# Heating.net
KiCad netlist of a schematic drawn in Altium Designer
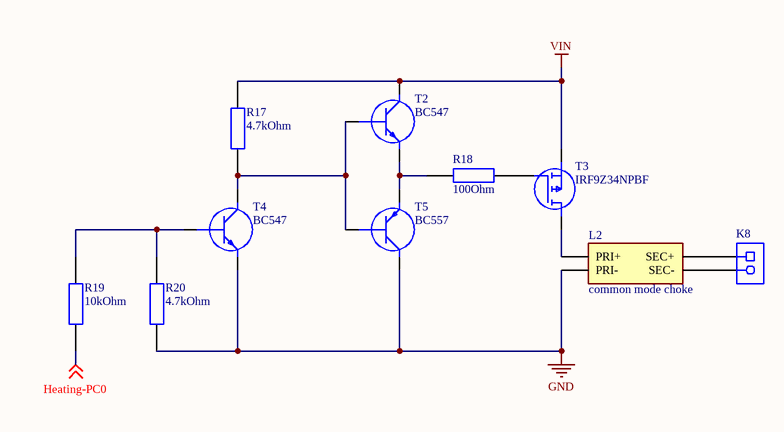
[diagram p0: Heating.SchDoc]

(export (version "E")
  (design (tool "Eeschema 10.0.6"))
  (components
    (comp (ref "K8")
      (value "1729128")
      (footprint "2-pin terminal block")
      (description "PCB Terminal Block, 13.5 A, 400 V, 2-Pin THD, RoHS, Bulk")
      (fields (field (name "MANUFACTURER") "Phoenix Contact"))
      (libsource (lib "Schlib1") (part "MKDSN 1,5/ 2-5,08"))
    )
    (comp (ref "L2")
      (value "common mode choke")
      (footprint "common mode choke")
      (description "Inductor")
      (fields (field (name "MANUFACTURER_PART_NUMBER") "CM2545X171B-10"))
      (libsource (lib "Schlib1") (part "common mode choke"))
    )
    (comp (ref "R17")
      (value "4.7kOhm")
      (footprint "resistor")
      (description "Resistor")
      (fields
        (field (name "MOUSER2 PART NUMBER") "603-CFR-25JT-52-4K7")
        (field (name "MANUFACTURER_PART_NUMBER") "CFR-25JT-52-4K7")
      )
      (libsource (lib "Schlib1") (part "4.7kOhm resistor"))
    )
    (comp (ref "R18")
      (value "100Ohm")
      (footprint "resistor")
      (description "Resistor")
      (fields
        (field (name "MOUSER2 PART NUMBER") "603-CFR-25JR-52100R")
        (field (name "MANUFACTURER_PART_NUMBER") "CFR-25JR-52-100R")
      )
      (libsource (lib "Schlib1") (part "100Ohm resistor"))
    )
    (comp (ref "R19")
      (value "10kOhm")
      (footprint "resistor")
      (description "Resistor")
      (fields (field (name "MANUFACTURER_PART_NUMBER") "CFR-25JT-52-10K"))
      (libsource (lib "Schlib1") (part "10kOhm resistor"))
    )
    (comp (ref "R20")
      (value "4.7kOhm")
      (footprint "resistor")
      (description "Resistor")
      (fields
        (field (name "MOUSER2 PART NUMBER") "603-CFR-25JT-52-4K7")
        (field (name "MANUFACTURER_PART_NUMBER") "CFR-25JT-52-4K7")
      )
      (libsource (lib "Schlib1") (part "4.7kOhm resistor"))
    )
    (comp (ref "T2")
      (value "BC547")
      (footprint "PcbLib1:BC547CBU")
      (description "Transistor BJT NPN")
      (fields (field (name "MANUFACTURER_PART_NUMBER") "BC547CBU"))
      (libsource (lib "Schlib1") (part "BC547"))
    )
    (comp (ref "T3")
      (value "IRF9Z34NPBF")
      (footprint "PcbLib1:TO254P469X1042X1967-3P")
      (description "MOSFET (P-Channel)")
      (fields (field (name "MOUSER2 PART NUMBER") "942-IRF9Z34NPBF"))
      (libsource (lib "Schlib1") (part "IRF9Z34NPBF"))
    )
    (comp (ref "T4")
      (value "BC547")
      (footprint "PcbLib1:BC547CBU")
      (description "Transistor BJT NPN")
      (fields (field (name "MANUFACTURER_PART_NUMBER") "BC547CBU"))
      (libsource (lib "Schlib1") (part "BC547"))
    )
    (comp (ref "T5")
      (value "BC557")
      (footprint "PcbLib1:BC33740TA")
      (description "Transistor BJT PNP")
      (fields
        (field (name "MOUSER2 PART NUMBER") "512-BC557ATA")
        (field (name "MANUFACTURER_PART_NUMBER") "BC557ATA")
      )
      (libsource (lib "Schlib1") (part "BC557"))
    )
  )
  (nets
    (net (code "1") (name "GND") (class "Default")
      (node (ref "L2") (pin "4") (pinfunction "PRI-_4") (pintype "passive"))
      (node (ref "R20") (pin "1") (pinfunction "1_1") (pintype "passive"))
      (node (ref "T4") (pin "3") (pinfunction "E_3") (pintype "passive"))
      (node (ref "T5") (pin "1") (pinfunction "C_1") (pintype "passive"))
    )
    (net (code "2") (name "Heating-PC0") (class "Default")
      (node (ref "R19") (pin "2") (pinfunction "2_2") (pintype "passive"))
    )
    (net (code "3") (name "Net-(L2-PRI+)") (class "Default")
      (node (ref "L2") (pin "1") (pinfunction "PRI+_1") (pintype "passive"))
      (node (ref "T3") (pin "3") (pinfunction "D_3") (pintype "passive"))
    )
    (net (code "4") (name "Net-(L2-SEC+)") (class "Default")
      (node (ref "K8") (pin "1") (pinfunction "1_1") (pintype "passive"))
      (node (ref "L2") (pin "2") (pinfunction "SEC+_2") (pintype "passive"))
    )
    (net (code "5") (name "Net-(L2-SEC-)") (class "Default")
      (node (ref "K8") (pin "2") (pinfunction "2_2") (pintype "passive"))
      (node (ref "L2") (pin "3") (pinfunction "SEC-_3") (pintype "passive"))
    )
    (net (code "6") (name "Net-(T2-B)") (class "Default")
      (node (ref "R17") (pin "1") (pinfunction "1_1") (pintype "passive"))
      (node (ref "T2") (pin "2") (pinfunction "B_2") (pintype "passive"))
      (node (ref "T4") (pin "1") (pinfunction "C_1") (pintype "passive"))
      (node (ref "T5") (pin "2") (pinfunction "B_2") (pintype "passive"))
    )
    (net (code "7") (name "Net-(T2-E)") (class "Default")
      (node (ref "R18") (pin "1") (pinfunction "1_1") (pintype "passive"))
      (node (ref "T2") (pin "3") (pinfunction "E_3") (pintype "passive"))
      (node (ref "T5") (pin "3") (pinfunction "E_3") (pintype "passive"))
    )
    (net (code "8") (name "Net-(T3-G)") (class "Default")
      (node (ref "R18") (pin "2") (pinfunction "2_2") (pintype "passive"))
      (node (ref "T3") (pin "1") (pinfunction "G_1") (pintype "passive"))
    )
    (net (code "9") (name "Net-(T4-B)") (class "Default")
      (node (ref "R19") (pin "1") (pinfunction "1_1") (pintype "passive"))
      (node (ref "R20") (pin "2") (pinfunction "2_2") (pintype "passive"))
      (node (ref "T4") (pin "2") (pinfunction "B_2") (pintype "passive"))
    )
    (net (code "10") (name "VIN") (class "Default")
      (node (ref "R17") (pin "2") (pinfunction "2_2") (pintype "passive"))
      (node (ref "T2") (pin "1") (pinfunction "C_1") (pintype "passive"))
      (node (ref "T3") (pin "2") (pinfunction "S_2") (pintype "passive"))
    )
  )
)
